# IR_hub.net
KiCad netlist of a schematic drawn in EAGLE
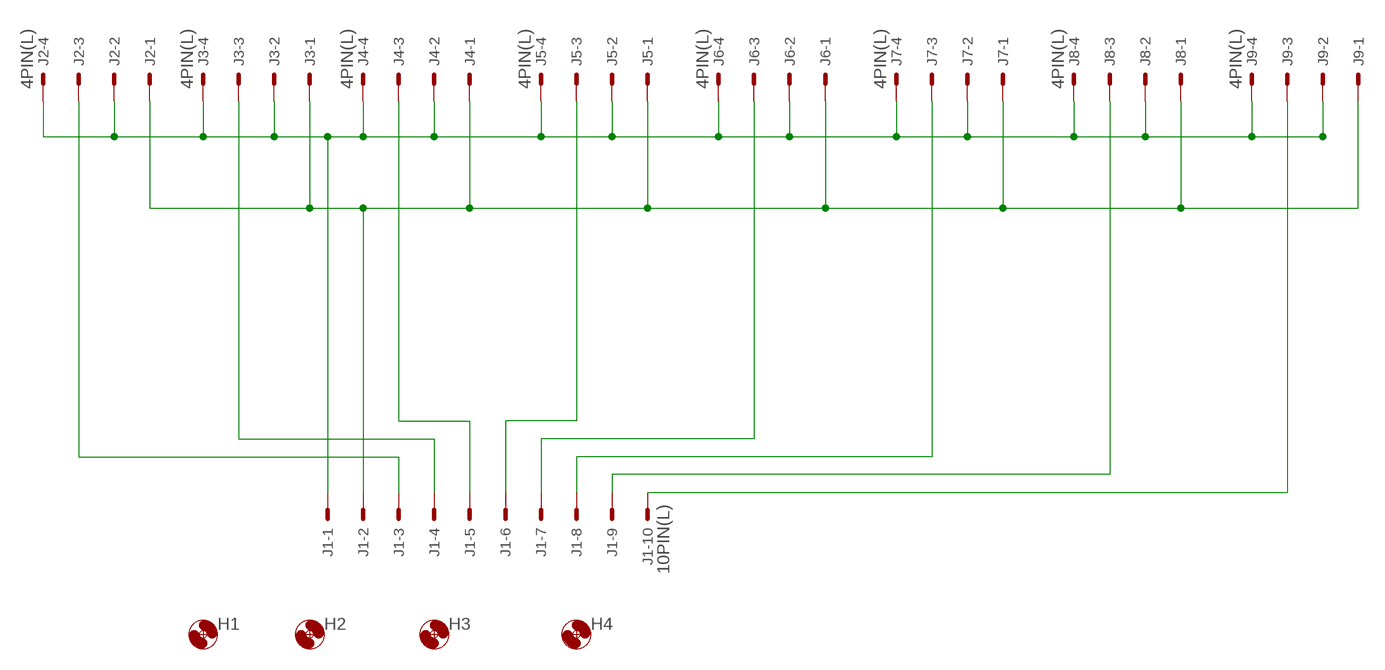
[diagram p0: schematic, sheet 1]

(export (version "E")
  (design (tool "Eeschema 10.0.6"))
  (components
    (comp (ref "H1")
      (value "HOLE3.3M3BOLT")
      (footprint "eagle-import:HOLE3.3")
      (libsource (lib "eagle-import") (part "HOLE3.3M3BOLT"))
    )
    (comp (ref "H2")
      (value "HOLE3.3M3BOLT")
      (footprint "eagle-import:HOLE3.3")
      (libsource (lib "eagle-import") (part "HOLE3.3M3BOLT"))
    )
    (comp (ref "H3")
      (value "HOLE3.3M3BOLT")
      (footprint "eagle-import:HOLE3.3")
      (libsource (lib "eagle-import") (part "HOLE3.3M3BOLT"))
    )
    (comp (ref "H4")
      (value "HOLE3.3M3BOLT")
      (footprint "eagle-import:HOLE3.3")
      (libsource (lib "eagle-import") (part "HOLE3.3M3BOLT"))
    )
    (comp (ref "J1")
      (value "10PIN(L)")
      (footprint "eagle-import:10PL")
      (libsource (lib "eagle-import") (part "10PIN(L)"))
    )
    (comp (ref "J2")
      (value "4PIN(L)")
      (footprint "eagle-import:4PL")
      (libsource (lib "eagle-import") (part "4PIN(L)"))
    )
    (comp (ref "J3")
      (value "4PIN(L)")
      (footprint "eagle-import:4PL")
      (libsource (lib "eagle-import") (part "4PIN(L)"))
    )
    (comp (ref "J4")
      (value "4PIN(L)")
      (footprint "eagle-import:4PL")
      (libsource (lib "eagle-import") (part "4PIN(L)"))
    )
    (comp (ref "J5")
      (value "4PIN(L)")
      (footprint "eagle-import:4PL")
      (libsource (lib "eagle-import") (part "4PIN(L)"))
    )
    (comp (ref "J6")
      (value "4PIN(L)")
      (footprint "eagle-import:4PL")
      (libsource (lib "eagle-import") (part "4PIN(L)"))
    )
    (comp (ref "J7")
      (value "4PIN(L)")
      (footprint "eagle-import:4PL")
      (libsource (lib "eagle-import") (part "4PIN(L)"))
    )
    (comp (ref "J8")
      (value "4PIN(L)")
      (footprint "eagle-import:4PL")
      (libsource (lib "eagle-import") (part "4PIN(L)"))
    )
    (comp (ref "J9")
      (value "4PIN(L)")
      (footprint "eagle-import:4PL")
      (libsource (lib "eagle-import") (part "4PIN(L)"))
    )
  )
  (nets
    (net (code "1") (name "Net-(J1A-S)") (class "Default")
      (node (ref "J1") (pin "1") (pinfunction "S_1") (pintype "passive"))
      (node (ref "J2") (pin "2") (pinfunction "S_2") (pintype "passive"))
      (node (ref "J2") (pin "4") (pinfunction "S_4") (pintype "passive"))
      (node (ref "J3") (pin "2") (pinfunction "S_2") (pintype "passive"))
      (node (ref "J3") (pin "4") (pinfunction "S_4") (pintype "passive"))
      (node (ref "J4") (pin "2") (pinfunction "S_2") (pintype "passive"))
      (node (ref "J4") (pin "4") (pinfunction "S_4") (pintype "passive"))
      (node (ref "J5") (pin "2") (pinfunction "S_2") (pintype "passive"))
      (node (ref "J5") (pin "4") (pinfunction "S_4") (pintype "passive"))
      (node (ref "J6") (pin "2") (pinfunction "S_2") (pintype "passive"))
      (node (ref "J6") (pin "4") (pinfunction "S_4") (pintype "passive"))
      (node (ref "J7") (pin "2") (pinfunction "S_2") (pintype "passive"))
      (node (ref "J7") (pin "4") (pinfunction "S_4") (pintype "passive"))
      (node (ref "J8") (pin "2") (pinfunction "S_2") (pintype "passive"))
      (node (ref "J8") (pin "4") (pinfunction "S_4") (pintype "passive"))
      (node (ref "J9") (pin "2") (pinfunction "S_2") (pintype "passive"))
      (node (ref "J9") (pin "4") (pinfunction "S_4") (pintype "passive"))
    )
    (net (code "2") (name "Net-(J1B-S)") (class "Default")
      (node (ref "J1") (pin "10") (pinfunction "S_10") (pintype "passive"))
      (node (ref "J9") (pin "3") (pinfunction "S_3") (pintype "passive"))
    )
    (net (code "3") (name "Net-(J1C-S)") (class "Default")
      (node (ref "J1") (pin "2") (pinfunction "S_2") (pintype "passive"))
      (node (ref "J2") (pin "1") (pinfunction "S_1") (pintype "passive"))
      (node (ref "J3") (pin "1") (pinfunction "S_1") (pintype "passive"))
      (node (ref "J4") (pin "1") (pinfunction "S_1") (pintype "passive"))
      (node (ref "J5") (pin "1") (pinfunction "S_1") (pintype "passive"))
      (node (ref "J6") (pin "1") (pinfunction "S_1") (pintype "passive"))
      (node (ref "J7") (pin "1") (pinfunction "S_1") (pintype "passive"))
      (node (ref "J8") (pin "1") (pinfunction "S_1") (pintype "passive"))
      (node (ref "J9") (pin "1") (pinfunction "S_1") (pintype "passive"))
    )
    (net (code "4") (name "Net-(J1D-S)") (class "Default")
      (node (ref "J1") (pin "3") (pinfunction "S_3") (pintype "passive"))
      (node (ref "J2") (pin "3") (pinfunction "S_3") (pintype "passive"))
    )
    (net (code "5") (name "Net-(J1E-S)") (class "Default")
      (node (ref "J1") (pin "4") (pinfunction "S_4") (pintype "passive"))
      (node (ref "J3") (pin "3") (pinfunction "S_3") (pintype "passive"))
    )
    (net (code "6") (name "Net-(J1F-S)") (class "Default")
      (node (ref "J1") (pin "5") (pinfunction "S_5") (pintype "passive"))
      (node (ref "J4") (pin "3") (pinfunction "S_3") (pintype "passive"))
    )
    (net (code "7") (name "Net-(J1G-S)") (class "Default")
      (node (ref "J1") (pin "6") (pinfunction "S_6") (pintype "passive"))
      (node (ref "J5") (pin "3") (pinfunction "S_3") (pintype "passive"))
    )
    (net (code "8") (name "Net-(J1H-S)") (class "Default")
      (node (ref "J1") (pin "7") (pinfunction "S_7") (pintype "passive"))
      (node (ref "J6") (pin "3") (pinfunction "S_3") (pintype "passive"))
    )
    (net (code "9") (name "Net-(J1I-S)") (class "Default")
      (node (ref "J1") (pin "8") (pinfunction "S_8") (pintype "passive"))
      (node (ref "J7") (pin "3") (pinfunction "S_3") (pintype "passive"))
    )
    (net (code "10") (name "Net-(J1J-S)") (class "Default")
      (node (ref "J1") (pin "9") (pinfunction "S_9") (pintype "passive"))
      (node (ref "J8") (pin "3") (pinfunction "S_3") (pintype "passive"))
    )
  )
)
